# 1-Schematic_EMWAVER_V1_2.net
KiCad netlist of a schematic drawn in EasyEDA
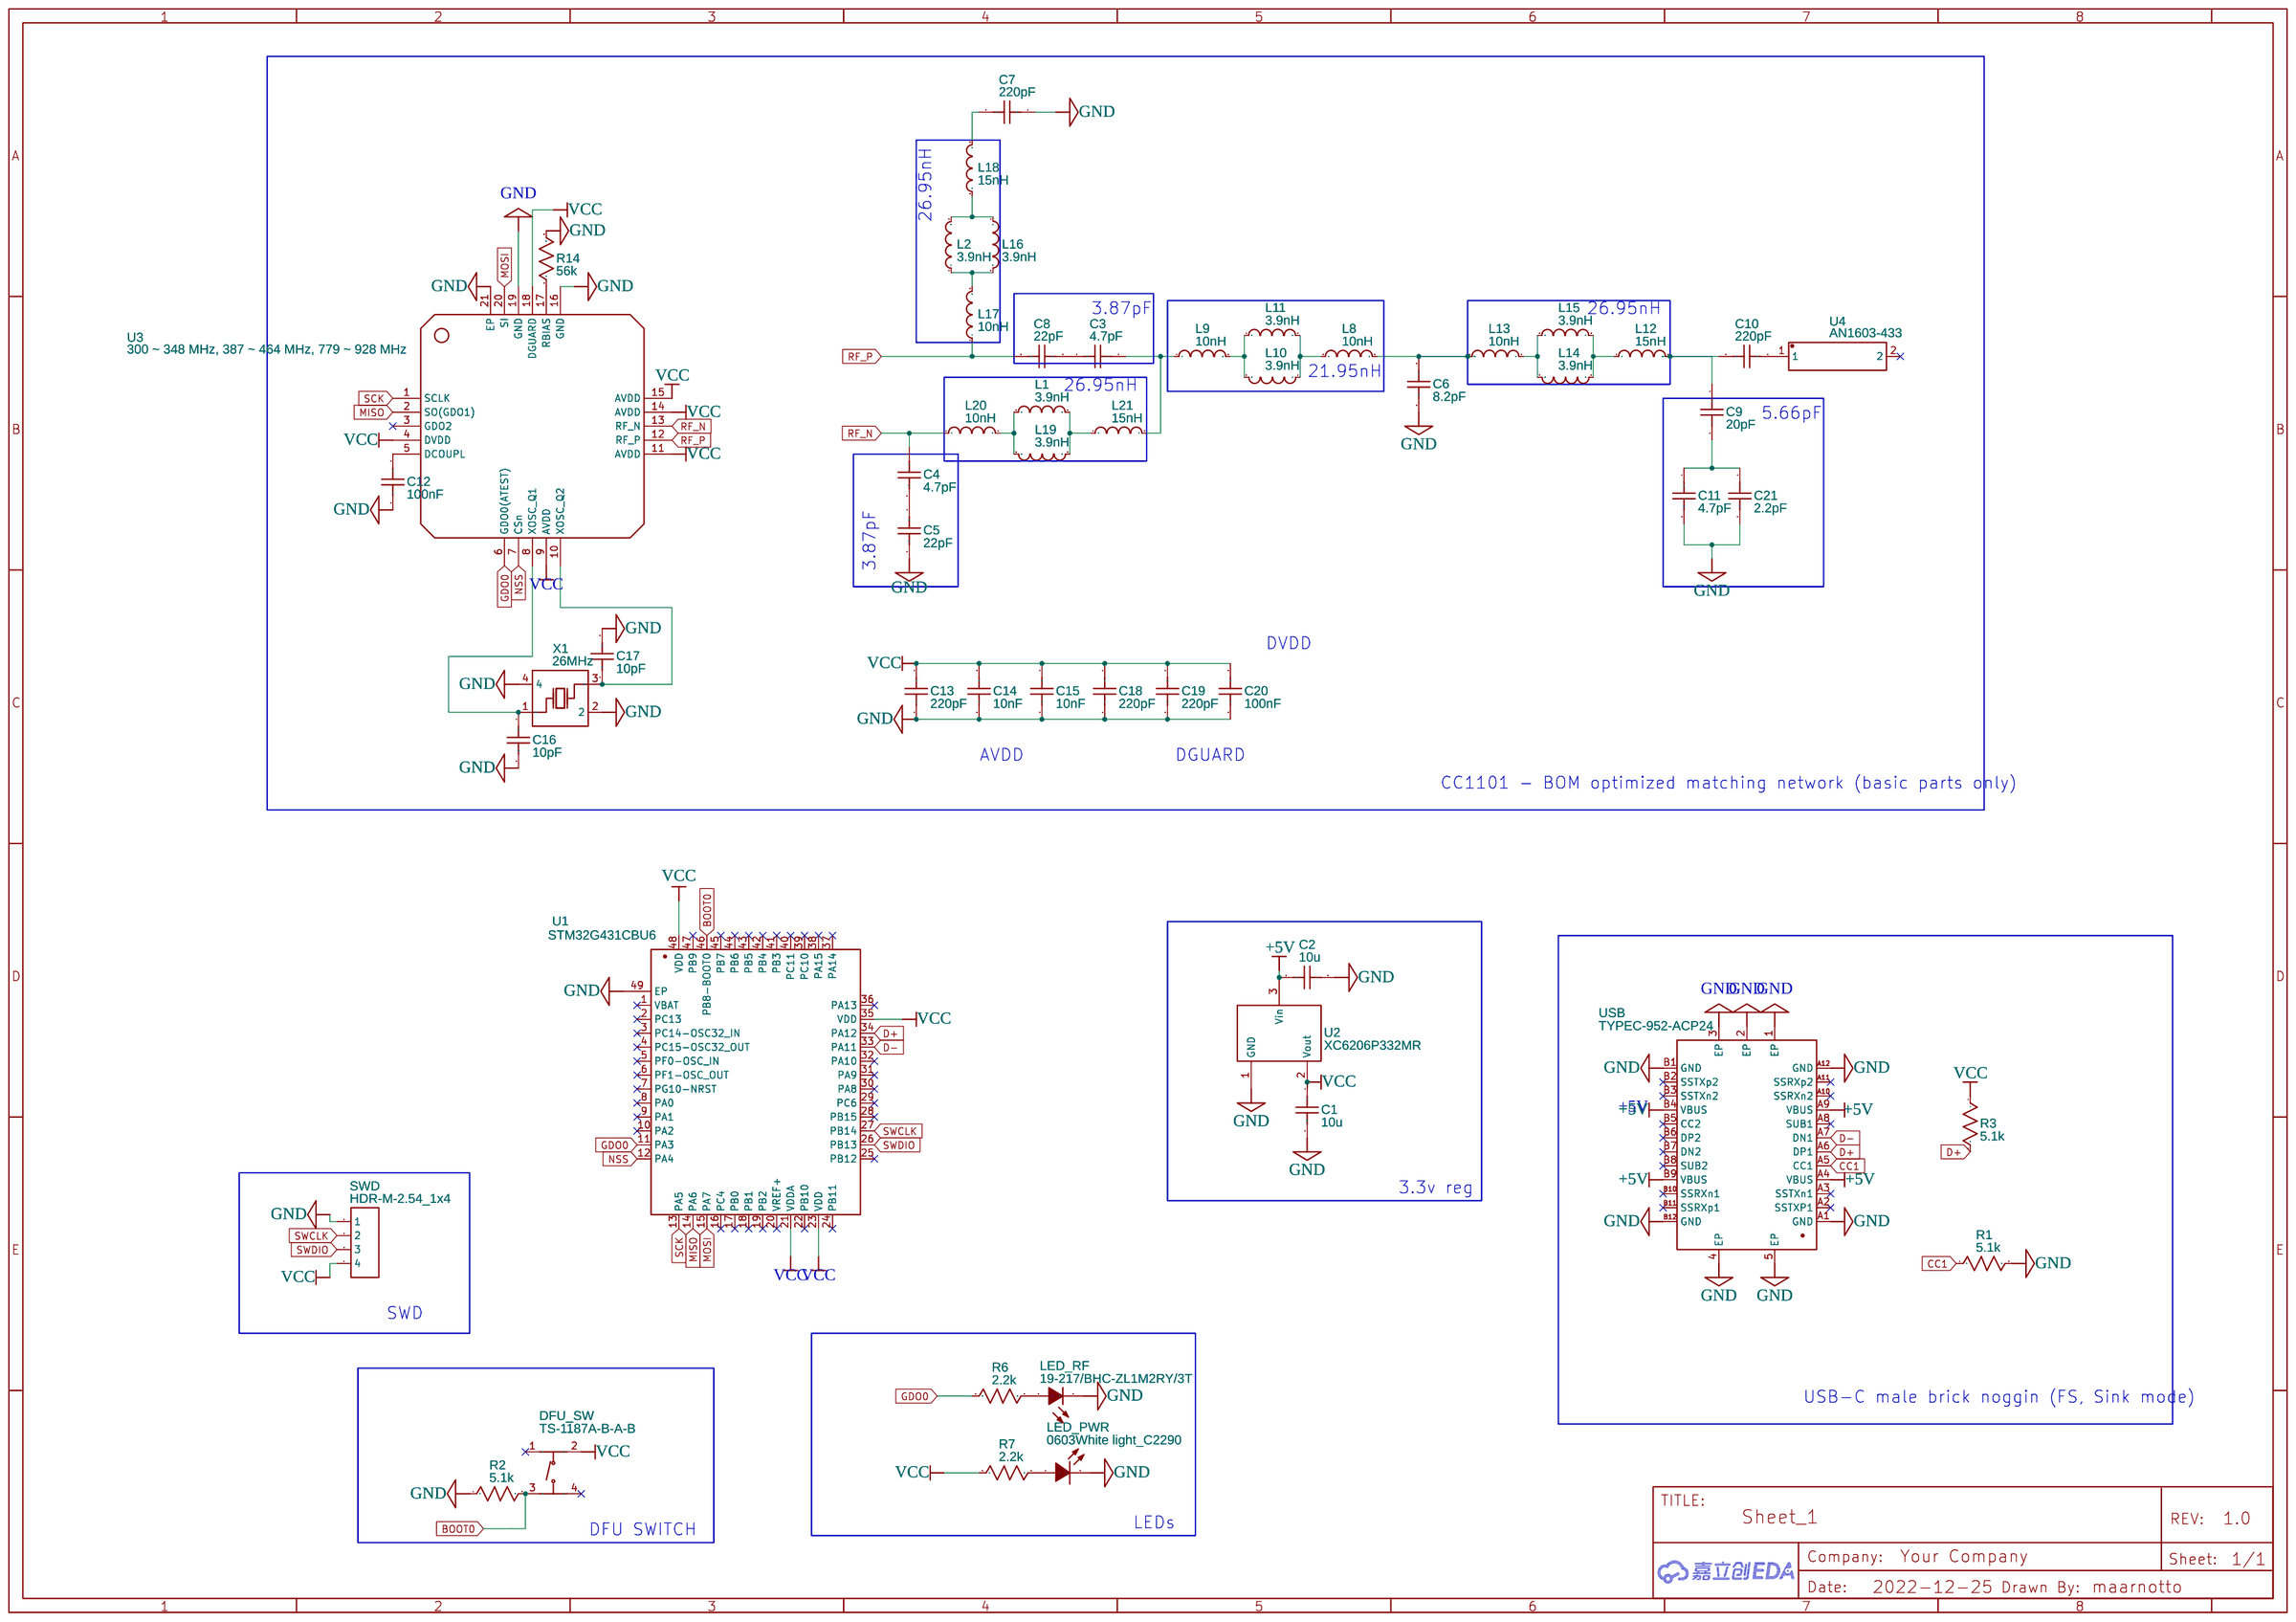
[diagram p0: schematic sheet]

(export (version "E")
  (design (tool "Eeschema 10.0.6"))
  (components
    (comp (ref "C1") (value "10u") (libsource (lib "") (part "C_0603_US_1")))
    (comp (ref "C2") (value "10u") (libsource (lib "") (part "C_0603_US")))
    (comp (ref "C3") (value "4.7pF") (libsource (lib "") (part "C_0402_US_2")))
    (comp (ref "C4") (value "4.7pF") (libsource (lib "") (part "C_0402_US")))
    (comp (ref "C5") (value "22pF") (libsource (lib "") (part "C_0402_US")))
    (comp (ref "C6") (value "8.2pF") (libsource (lib "") (part "C_0603_US_1")))
    (comp (ref "C7") (value "220pF") (libsource (lib "") (part "C_0402_US_2")))
    (comp (ref "C8") (value "22pF") (libsource (lib "") (part "C_0402_US_2")))
    (comp (ref "C9") (value "20pF") (libsource (lib "") (part "C_0402_US")))
    (comp (ref "C10") (value "220pF") (libsource (lib "") (part "C_0402_US_2")))
    (comp (ref "C11") (value "4.7pF") (libsource (lib "") (part "C_0402_US")))
    (comp (ref "C12") (value "100nF") (libsource (lib "") (part "C_0402_US")))
    (comp (ref "C13") (value "220pF") (libsource (lib "") (part "C_0402_US")))
    (comp (ref "C14") (value "10nF") (libsource (lib "") (part "C_0402_US")))
    (comp (ref "C15") (value "10nF") (libsource (lib "") (part "C_0402_US")))
    (comp (ref "C16") (value "10pF") (libsource (lib "") (part "C_0402_US")))
    (comp (ref "C17") (value "10pF") (libsource (lib "") (part "C_0402_US_1")))
    (comp (ref "C18") (value "220pF") (libsource (lib "") (part "C_0402_US")))
    (comp (ref "C19") (value "220pF") (libsource (lib "") (part "C_0402_US")))
    (comp (ref "C20") (value "100nF") (libsource (lib "") (part "C_0402_US")))
    (comp (ref "C21") (value "2.2pF") (libsource (lib "") (part "C_0402_US")))
    (comp (ref "DFU_SW")
      (value "TS-1187A-B-A-B")
      (fields (field (name "BOM_Supplier Part") "C318884"))
      (libsource (lib "") (part "TS-1187A-B-A-B"))
    )
    (comp (ref "L1")
      (value "3.9nH")
      (fields (field (name "BOM_Supplier Part") "C14033"))
      (libsource (lib "") (part "L0402_US_1"))
    )
    (comp (ref "L2")
      (value "3.9nH")
      (fields (field (name "BOM_Supplier Part") "C14033"))
      (libsource (lib "") (part "L0402_US"))
    )
    (comp (ref "L8")
      (value "10nH")
      (fields (field (name "BOM_Supplier Part") "C27147"))
      (libsource (lib "") (part "L0402_US_1"))
    )
    (comp (ref "L9")
      (value "10nH")
      (fields (field (name "BOM_Supplier Part") "C27147"))
      (libsource (lib "") (part "L0402_US_1"))
    )
    (comp (ref "L10")
      (value "3.9nH")
      (fields (field (name "BOM_Supplier Part") "C14033"))
      (libsource (lib "") (part "L0402_US_2"))
    )
    (comp (ref "L11")
      (value "3.9nH")
      (fields (field (name "BOM_Supplier Part") "C14033"))
      (libsource (lib "") (part "L0402_US_1"))
    )
    (comp (ref "L12")
      (value "15nH")
      (fields (field (name "BOM_Supplier Part") "C27143"))
      (libsource (lib "") (part "L0402_US_3"))
    )
    (comp (ref "L13")
      (value "10nH")
      (fields (field (name "BOM_Supplier Part") "C27147"))
      (libsource (lib "") (part "L0402_US_3"))
    )
    (comp (ref "L14")
      (value "3.9nH")
      (fields (field (name "BOM_Supplier Part") "C14033"))
      (libsource (lib "") (part "L0402_US_5"))
    )
    (comp (ref "L15")
      (value "3.9nH")
      (fields (field (name "BOM_Supplier Part") "C14033"))
      (libsource (lib "") (part "L0402_US_3"))
    )
    (comp (ref "L16")
      (value "3.9nH")
      (fields (field (name "BOM_Supplier Part") "C14033"))
      (libsource (lib "") (part "L0402_US_6"))
    )
    (comp (ref "L17")
      (value "10nH")
      (fields (field (name "BOM_Supplier Part") "C27147"))
      (libsource (lib "") (part "L0402_US"))
    )
    (comp (ref "L18")
      (value "15nH")
      (fields (field (name "BOM_Supplier Part") "C27143"))
      (libsource (lib "") (part "L0402_US_4"))
    )
    (comp (ref "L19")
      (value "3.9nH")
      (fields (field (name "BOM_Supplier Part") "C14033"))
      (libsource (lib "") (part "L0402_US_2"))
    )
    (comp (ref "L20")
      (value "10nH")
      (fields (field (name "BOM_Supplier Part") "C27147"))
      (libsource (lib "") (part "L0402_US_1"))
    )
    (comp (ref "L21")
      (value "15nH")
      (fields (field (name "BOM_Supplier Part") "C27143"))
      (libsource (lib "") (part "L0402_US_1"))
    )
    (comp (ref "LED_PWR")
      (value "0603White light_C2290")
      (fields (field (name "BOM_Manufacturer Part") "KT-0603白灯") (field (name "BOM_Supplier Part") "C2290"))
      (libsource (lib "") (part "0603White light_C2290"))
    )
    (comp (ref "LED_RF")
      (value "19-217/BHC-ZL1M2RY/3T")
      (fields (field (name "BOM_Supplier Part") "C72041"))
      (libsource (lib "") (part "19-217/BHC-ZL1M2RY/3T"))
    )
    (comp (ref "R1") (value "5.1k") (libsource (lib "") (part "R_0603_US")))
    (comp (ref "R2") (value "5.1k") (libsource (lib "") (part "R_0603_US")))
    (comp (ref "R3") (value "5.1k") (libsource (lib "") (part "R_0603_US_1")))
    (comp (ref "R6") (value "2.2k") (libsource (lib "") (part "R_0603_US")))
    (comp (ref "R7") (value "2.2k") (libsource (lib "") (part "R_0603_US")))
    (comp (ref "R14") (value "56k") (libsource (lib "") (part "R_0402_US")))
    (comp (ref "SWD")
      (value "HDR-M-2.54_1x4")
      (fields (field (name "BOM_Supplier Part") "C124378"))
      (libsource (lib "") (part "HDR-M-2.54_1x4"))
    )
    (comp (ref "U1")
      (value "STM32G431CBU6")
      (fields (field (name "BOM_Supplier Part") "C529356"))
      (libsource (lib "") (part "STM32G431CBU6"))
    )
    (comp (ref "U2")
      (value "XC6206P332MR")
      (fields (field (name "BOM_Supplier Part") "C5446"))
      (libsource (lib "") (part "XC6206P332MR"))
    )
    (comp (ref "U3")
      (value "300 ~ 348 MHz, 387 ~ 464 MHz, 779 ~ 928 MHz")
      (fields (field (name "BOM_Manufacturer Part") "CC1101RGPR") (field (name "BOM_Supplier Part") "C29953"))
      (libsource (lib "") (part "CC1101RGPR"))
    )
    (comp (ref "U4")
      (value "AN1603-433")
      (fields (field (name "BOM_Supplier Part") "C122806"))
      (libsource (lib "") (part "AN1603-433"))
    )
    (comp (ref "USB")
      (value "TYPEC-952-ACP24")
      (fields (field (name "BOM_Supplier Part") "C2840398"))
      (libsource (lib "") (part "TYPEC-952-ACP24"))
    )
    (comp (ref "X1")
      (value "26MHz")
      (fields
        (field (name "BOM_Manufacturer Part") "3S26000333")
        (field (name "BOM_Supplier Part") "C431163")
      )
      (libsource (lib "") (part "3S26000333"))
    )
  )
  (nets
    (net (code "1") (name "+5V") (class "Default")
      (node (ref "C2") (pin "2") (pinfunction "2_2") (pintype "unspecified"))
      (node (ref "U2") (pin "3") (pinfunction "Vin_3") (pintype "unspecified"))
      (node (ref "USB") (pin "A4") (pinfunction "VBUS_A4") (pintype "unspecified"))
      (node (ref "USB") (pin "A9") (pinfunction "VBUS_A9") (pintype "unspecified"))
      (node (ref "USB") (pin "B4") (pinfunction "VBUS_B4") (pintype "unspecified"))
      (node (ref "USB") (pin "B9") (pinfunction "VBUS_B9") (pintype "unspecified"))
    )
    (net (code "2") (name "BOOT0") (class "Default")
      (node (ref "DFU_SW") (pin "3") (pinfunction "C_3") (pintype "unspecified"))
      (node (ref "R2") (pin "2") (pinfunction "2_2") (pintype "unspecified"))
      (node (ref "U1") (pin "46") (pinfunction "PB8-BOOT0_46") (pintype "unspecified"))
    )
    (net (code "3") (name "CC1") (class "Default")
      (node (ref "R1") (pin "1") (pinfunction "1_1") (pintype "unspecified"))
      (node (ref "USB") (pin "A5") (pinfunction "CC1_A5") (pintype "unspecified"))
    )
    (net (code "4") (name "D+") (class "Default")
      (node (ref "R3") (pin "2") (pinfunction "2_2") (pintype "unspecified"))
      (node (ref "U1") (pin "34") (pinfunction "PA12_34") (pintype "unspecified"))
      (node (ref "USB") (pin "A6") (pinfunction "DP1_A6") (pintype "unspecified"))
    )
    (net (code "5") (name "D-") (class "Default")
      (node (ref "U1") (pin "33") (pinfunction "PA11_33") (pintype "unspecified"))
      (node (ref "USB") (pin "A7") (pinfunction "DN1_A7") (pintype "unspecified"))
    )
    (net (code "6") (name "GDO0") (class "Default")
      (node (ref "R6") (pin "1") (pinfunction "1_1") (pintype "unspecified"))
      (node (ref "U1") (pin "11") (pinfunction "PA3_11") (pintype "unspecified"))
      (node (ref "U3") (pin "6") (pinfunction "GDO0(ATEST)_6") (pintype "unspecified"))
    )
    (net (code "7") (name "GND") (class "Default")
      (node (ref "C1") (pin "2") (pinfunction "2_2") (pintype "unspecified"))
      (node (ref "C11") (pin "2") (pinfunction "2_2") (pintype "unspecified"))
      (node (ref "C12") (pin "2") (pinfunction "2_2") (pintype "unspecified"))
      (node (ref "C13") (pin "2") (pinfunction "2_2") (pintype "unspecified"))
      (node (ref "C14") (pin "2") (pinfunction "2_2") (pintype "unspecified"))
      (node (ref "C15") (pin "2") (pinfunction "2_2") (pintype "unspecified"))
      (node (ref "C16") (pin "2") (pinfunction "2_2") (pintype "unspecified"))
      (node (ref "C17") (pin "2") (pinfunction "2_2") (pintype "unspecified"))
      (node (ref "C18") (pin "2") (pinfunction "2_2") (pintype "unspecified"))
      (node (ref "C19") (pin "2") (pinfunction "2_2") (pintype "unspecified"))
      (node (ref "C2") (pin "1") (pinfunction "1_1") (pintype "unspecified"))
      (node (ref "C20") (pin "2") (pinfunction "2_2") (pintype "unspecified"))
      (node (ref "C21") (pin "2") (pinfunction "2_2") (pintype "unspecified"))
      (node (ref "C5") (pin "2") (pinfunction "2_2") (pintype "unspecified"))
      (node (ref "C6") (pin "2") (pinfunction "2_2") (pintype "unspecified"))
      (node (ref "C7") (pin "1") (pinfunction "1_1") (pintype "unspecified"))
      (node (ref "LED_PWR") (pin "2") (pinfunction "K_2") (pintype "unspecified"))
      (node (ref "LED_RF") (pin "1") (pinfunction "C_1") (pintype "input"))
      (node (ref "R1") (pin "2") (pinfunction "2_2") (pintype "unspecified"))
      (node (ref "R14") (pin "2") (pinfunction "2_2") (pintype "unspecified"))
      (node (ref "R2") (pin "1") (pinfunction "1_1") (pintype "unspecified"))
      (node (ref "SWD") (pin "1") (pinfunction "1_1") (pintype "unspecified"))
      (node (ref "U1") (pin "49") (pinfunction "EP_49") (pintype "unspecified"))
      (node (ref "U2") (pin "1") (pinfunction "GND_1") (pintype "unspecified"))
      (node (ref "U3") (pin "16") (pinfunction "GND_16") (pintype "unspecified"))
      (node (ref "U3") (pin "19") (pinfunction "GND_19") (pintype "unspecified"))
      (node (ref "U3") (pin "21") (pinfunction "EP_21") (pintype "unspecified"))
      (node (ref "USB") (pin "1") (pinfunction "EP_1") (pintype "unspecified"))
      (node (ref "USB") (pin "2") (pinfunction "EP_2") (pintype "unspecified"))
      (node (ref "USB") (pin "3") (pinfunction "EP_3") (pintype "unspecified"))
      (node (ref "USB") (pin "4") (pinfunction "EP_4") (pintype "unspecified"))
      (node (ref "USB") (pin "5") (pinfunction "EP_5") (pintype "unspecified"))
      (node (ref "USB") (pin "A1") (pinfunction "GND_A1") (pintype "unspecified"))
      (node (ref "USB") (pin "A12") (pinfunction "GND_A12") (pintype "unspecified"))
      (node (ref "USB") (pin "B1") (pinfunction "GND_B1") (pintype "unspecified"))
      (node (ref "USB") (pin "B12") (pinfunction "GND_B12") (pintype "unspecified"))
      (node (ref "X1") (pin "2") (pinfunction "2_2") (pintype "unspecified"))
      (node (ref "X1") (pin "4") (pinfunction "4_4") (pintype "unspecified"))
    )
    (net (code "8") (name "MISO") (class "Default")
      (node (ref "U1") (pin "14") (pinfunction "PA6_14") (pintype "unspecified"))
      (node (ref "U3") (pin "2") (pinfunction "SO(GDO1)_2") (pintype "unspecified"))
    )
    (net (code "9") (name "MOSI") (class "Default")
      (node (ref "U1") (pin "15") (pinfunction "PA7_15") (pintype "unspecified"))
      (node (ref "U3") (pin "20") (pinfunction "SI_20") (pintype "unspecified"))
    )
    (net (code "10") (name "NSS") (class "Default")
      (node (ref "U1") (pin "12") (pinfunction "PA4_12") (pintype "unspecified"))
      (node (ref "U3") (pin "7") (pinfunction "CSn_7") (pintype "unspecified"))
    )
    (net (code "11") (name "Net-(C3-Pad1)") (class "Default")
      (node (ref "C3") (pin "1") (pinfunction "1_1") (pintype "unspecified"))
      (node (ref "L21") (pin "2") (pinfunction "2_2") (pintype "unspecified"))
      (node (ref "L9") (pin "1") (pinfunction "1_1") (pintype "unspecified"))
    )
    (net (code "12") (name "Net-(C3-Pad2)") (class "Default")
      (node (ref "C3") (pin "2") (pinfunction "2_2") (pintype "unspecified"))
      (node (ref "C8") (pin "1") (pinfunction "1_1") (pintype "unspecified"))
    )
    (net (code "13") (name "Net-(C4-Pad2)") (class "Default")
      (node (ref "C4") (pin "2") (pinfunction "2_2") (pintype "unspecified"))
      (node (ref "C5") (pin "1") (pinfunction "1_1") (pintype "unspecified"))
    )
    (net (code "14") (name "Net-(C6-Pad1)") (class "Default")
      (node (ref "C6") (pin "1") (pinfunction "1_1") (pintype "unspecified"))
      (node (ref "L13") (pin "1") (pinfunction "1_1") (pintype "unspecified"))
      (node (ref "L8") (pin "2") (pinfunction "2_2") (pintype "unspecified"))
    )
    (net (code "15") (name "Net-(C7-Pad2)") (class "Default")
      (node (ref "C7") (pin "2") (pinfunction "2_2") (pintype "unspecified"))
      (node (ref "L18") (pin "2") (pinfunction "2_2") (pintype "unspecified"))
    )
    (net (code "16") (name "Net-(C10-Pad1)") (class "Default")
      (node (ref "C10") (pin "1") (pinfunction "1_1") (pintype "unspecified"))
      (node (ref "U4") (pin "1") (pinfunction "1_1") (pintype "unspecified"))
    )
    (net (code "17") (name "Net-(C10-Pad2)") (class "Default")
      (node (ref "C10") (pin "2") (pinfunction "2_2") (pintype "unspecified"))
      (node (ref "C9") (pin "1") (pinfunction "1_1") (pintype "unspecified"))
      (node (ref "L12") (pin "2") (pinfunction "2_2") (pintype "unspecified"))
    )
    (net (code "18") (name "Net-(C11-Pad1)") (class "Default")
      (node (ref "C11") (pin "1") (pinfunction "1_1") (pintype "unspecified"))
      (node (ref "C21") (pin "1") (pinfunction "1_1") (pintype "unspecified"))
      (node (ref "C9") (pin "2") (pinfunction "2_2") (pintype "unspecified"))
    )
    (net (code "19") (name "Net-(L1-Pad1)") (class "Default")
      (node (ref "L1") (pin "1") (pinfunction "1_1") (pintype "unspecified"))
      (node (ref "L19") (pin "2") (pinfunction "2_2") (pintype "unspecified"))
      (node (ref "L20") (pin "2") (pinfunction "2_2") (pintype "unspecified"))
    )
    (net (code "20") (name "Net-(L1-Pad2)") (class "Default")
      (node (ref "L1") (pin "2") (pinfunction "2_2") (pintype "unspecified"))
      (node (ref "L19") (pin "1") (pinfunction "1_1") (pintype "unspecified"))
      (node (ref "L21") (pin "1") (pinfunction "1_1") (pintype "unspecified"))
    )
    (net (code "21") (name "Net-(L10-Pad1)") (class "Default")
      (node (ref "L10") (pin "1") (pinfunction "1_1") (pintype "unspecified"))
      (node (ref "L11") (pin "2") (pinfunction "2_2") (pintype "unspecified"))
      (node (ref "L8") (pin "1") (pinfunction "1_1") (pintype "unspecified"))
    )
    (net (code "22") (name "Net-(L10-Pad2)") (class "Default")
      (node (ref "L10") (pin "2") (pinfunction "2_2") (pintype "unspecified"))
      (node (ref "L11") (pin "1") (pinfunction "1_1") (pintype "unspecified"))
      (node (ref "L9") (pin "2") (pinfunction "2_2") (pintype "unspecified"))
    )
    (net (code "23") (name "Net-(L12-Pad1)") (class "Default")
      (node (ref "L12") (pin "1") (pinfunction "1_1") (pintype "unspecified"))
      (node (ref "L14") (pin "1") (pinfunction "1_1") (pintype "unspecified"))
      (node (ref "L15") (pin "2") (pinfunction "2_2") (pintype "unspecified"))
    )
    (net (code "24") (name "Net-(L13-Pad2)") (class "Default")
      (node (ref "L13") (pin "2") (pinfunction "2_2") (pintype "unspecified"))
      (node (ref "L14") (pin "2") (pinfunction "2_2") (pintype "unspecified"))
      (node (ref "L15") (pin "1") (pinfunction "1_1") (pintype "unspecified"))
    )
    (net (code "25") (name "Net-(L16-Pad1)") (class "Default")
      (node (ref "L16") (pin "1") (pinfunction "1_1") (pintype "unspecified"))
      (node (ref "L18") (pin "1") (pinfunction "1_1") (pintype "unspecified"))
      (node (ref "L2") (pin "2") (pinfunction "2_2") (pintype "unspecified"))
    )
    (net (code "26") (name "Net-(L16-Pad2)") (class "Default")
      (node (ref "L16") (pin "2") (pinfunction "2_2") (pintype "unspecified"))
      (node (ref "L17") (pin "2") (pinfunction "2_2") (pintype "unspecified"))
      (node (ref "L2") (pin "1") (pinfunction "1_1") (pintype "unspecified"))
    )
    (net (code "27") (name "Net-(LED_PWR-A)") (class "Default")
      (node (ref "LED_PWR") (pin "1") (pinfunction "A_1") (pintype "unspecified"))
      (node (ref "R7") (pin "2") (pinfunction "2_2") (pintype "unspecified"))
    )
    (net (code "28") (name "Net-(LED_RF-A)") (class "Default")
      (node (ref "LED_RF") (pin "2") (pinfunction "A_2") (pintype "input"))
      (node (ref "R6") (pin "2") (pinfunction "2_2") (pintype "unspecified"))
    )
    (net (code "29") (name "Net-(U3-DCOUPL)") (class "Default")
      (node (ref "C12") (pin "1") (pinfunction "1_1") (pintype "unspecified"))
      (node (ref "U3") (pin "5") (pinfunction "DCOUPL_5") (pintype "unspecified"))
    )
    (net (code "30") (name "Net-(U3-RBIAS)") (class "Default")
      (node (ref "R14") (pin "1") (pinfunction "1_1") (pintype "unspecified"))
      (node (ref "U3") (pin "17") (pinfunction "RBIAS_17") (pintype "unspecified"))
    )
    (net (code "31") (name "Net-(U3-XOSC_Q1)") (class "Default")
      (node (ref "C16") (pin "1") (pinfunction "1_1") (pintype "unspecified"))
      (node (ref "U3") (pin "8") (pinfunction "XOSC_Q1_8") (pintype "unspecified"))
      (node (ref "X1") (pin "1") (pinfunction "OSC1_1") (pintype "unspecified"))
    )
    (net (code "32") (name "Net-(U3-XOSC_Q2)") (class "Default")
      (node (ref "C17") (pin "1") (pinfunction "1_1") (pintype "unspecified"))
      (node (ref "U3") (pin "10") (pinfunction "XOSC_Q2_10") (pintype "unspecified"))
      (node (ref "X1") (pin "3") (pinfunction "OSC2_3") (pintype "unspecified"))
    )
    (net (code "33") (name "RF_N") (class "Default")
      (node (ref "C4") (pin "1") (pinfunction "1_1") (pintype "unspecified"))
      (node (ref "L20") (pin "1") (pinfunction "1_1") (pintype "unspecified"))
      (node (ref "U3") (pin "13") (pinfunction "RF_N_13") (pintype "unspecified"))
    )
    (net (code "34") (name "RF_P") (class "Default")
      (node (ref "C8") (pin "2") (pinfunction "2_2") (pintype "unspecified"))
      (node (ref "L17") (pin "1") (pinfunction "1_1") (pintype "unspecified"))
      (node (ref "U3") (pin "12") (pinfunction "RF_P_12") (pintype "unspecified"))
    )
    (net (code "35") (name "SCK") (class "Default")
      (node (ref "U1") (pin "13") (pinfunction "PA5_13") (pintype "unspecified"))
      (node (ref "U3") (pin "1") (pinfunction "SCLK_1") (pintype "unspecified"))
    )
    (net (code "36") (name "SWCLK") (class "Default")
      (node (ref "SWD") (pin "2") (pinfunction "2_2") (pintype "unspecified"))
      (node (ref "U1") (pin "27") (pinfunction "PB14_27") (pintype "unspecified"))
    )
    (net (code "37") (name "SWDIO") (class "Default")
      (node (ref "SWD") (pin "3") (pinfunction "3_3") (pintype "unspecified"))
      (node (ref "U1") (pin "26") (pinfunction "PB13_26") (pintype "unspecified"))
    )
    (net (code "38") (name "VCC") (class "Default")
      (node (ref "C1") (pin "1") (pinfunction "1_1") (pintype "unspecified"))
      (node (ref "C13") (pin "1") (pinfunction "1_1") (pintype "unspecified"))
      (node (ref "C14") (pin "1") (pinfunction "1_1") (pintype "unspecified"))
      (node (ref "C15") (pin "1") (pinfunction "1_1") (pintype "unspecified"))
      (node (ref "C18") (pin "1") (pinfunction "1_1") (pintype "unspecified"))
      (node (ref "C19") (pin "1") (pinfunction "1_1") (pintype "unspecified"))
      (node (ref "C20") (pin "1") (pinfunction "1_1") (pintype "unspecified"))
      (node (ref "DFU_SW") (pin "2") (pinfunction "B_2") (pintype "unspecified"))
      (node (ref "R3") (pin "1") (pinfunction "1_1") (pintype "unspecified"))
      (node (ref "R7") (pin "1") (pinfunction "1_1") (pintype "unspecified"))
      (node (ref "SWD") (pin "4") (pinfunction "4_4") (pintype "unspecified"))
      (node (ref "U1") (pin "21") (pinfunction "VDDA_21") (pintype "unspecified"))
      (node (ref "U1") (pin "23") (pinfunction "VDD_23") (pintype "unspecified"))
      (node (ref "U1") (pin "35") (pinfunction "VDD_35") (pintype "unspecified"))
      (node (ref "U1") (pin "48") (pinfunction "VDD_48") (pintype "unspecified"))
      (node (ref "U2") (pin "2") (pinfunction "Vout_2") (pintype "unspecified"))
      (node (ref "U3") (pin "11") (pinfunction "AVDD_11") (pintype "unspecified"))
      (node (ref "U3") (pin "14") (pinfunction "AVDD_14") (pintype "unspecified"))
      (node (ref "U3") (pin "15") (pinfunction "AVDD_15") (pintype "unspecified"))
      (node (ref "U3") (pin "18") (pinfunction "DGUARD_18") (pintype "unspecified"))
      (node (ref "U3") (pin "4") (pinfunction "DVDD_4") (pintype "unspecified"))
      (node (ref "U3") (pin "9") (pinfunction "AVDD_9") (pintype "unspecified"))
    )
    (net (code "39") (name "unconnected-(DFU_SW-A-Pad1)") (class "Default")
      (node (ref "DFU_SW") (pin "1") (pinfunction "A_1") (pintype "unspecified+no_connect"))
    )
    (net (code "40") (name "unconnected-(DFU_SW-D-Pad4)") (class "Default")
      (node (ref "DFU_SW") (pin "4") (pinfunction "D_4") (pintype "unspecified+no_connect"))
    )
    (net (code "41") (name "unconnected-(U1-PA0-Pad8)") (class "Default")
      (node (ref "U1") (pin "8") (pinfunction "PA0_8") (pintype "unspecified+no_connect"))
    )
    (net (code "42") (name "unconnected-(U1-PA1-Pad9)") (class "Default")
      (node (ref "U1") (pin "9") (pinfunction "PA1_9") (pintype "unspecified+no_connect"))
    )
    (net (code "43") (name "unconnected-(U1-PA2-Pad10)") (class "Default")
      (node (ref "U1") (pin "10") (pinfunction "PA2_10") (pintype "unspecified+no_connect"))
    )
    (net (code "44") (name "unconnected-(U1-PA8-Pad30)") (class "Default")
      (node (ref "U1") (pin "30") (pinfunction "PA8_30") (pintype "unspecified+no_connect"))
    )
    (net (code "45") (name "unconnected-(U1-PA9-Pad31)") (class "Default")
      (node (ref "U1") (pin "31") (pinfunction "PA9_31") (pintype "unspecified+no_connect"))
    )
    (net (code "46") (name "unconnected-(U1-PA10-Pad32)") (class "Default")
      (node (ref "U1") (pin "32") (pinfunction "PA10_32") (pintype "unspecified+no_connect"))
    )
    (net (code "47") (name "unconnected-(U1-PA13-Pad36)") (class "Default")
      (node (ref "U1") (pin "36") (pinfunction "PA13_36") (pintype "unspecified+no_connect"))
    )
    (net (code "48") (name "unconnected-(U1-PA14-Pad37)") (class "Default")
      (node (ref "U1") (pin "37") (pinfunction "PA14_37") (pintype "unspecified+no_connect"))
    )
    (net (code "49") (name "unconnected-(U1-PA15-Pad38)") (class "Default")
      (node (ref "U1") (pin "38") (pinfunction "PA15_38") (pintype "unspecified+no_connect"))
    )
    (net (code "50") (name "unconnected-(U1-PB0-Pad17)") (class "Default")
      (node (ref "U1") (pin "17") (pinfunction "PB0_17") (pintype "unspecified+no_connect"))
    )
    (net (code "51") (name "unconnected-(U1-PB1-Pad18)") (class "Default")
      (node (ref "U1") (pin "18") (pinfunction "PB1_18") (pintype "unspecified+no_connect"))
    )
    (net (code "52") (name "unconnected-(U1-PB2-Pad19)") (class "Default")
      (node (ref "U1") (pin "19") (pinfunction "PB2_19") (pintype "unspecified+no_connect"))
    )
    (net (code "53") (name "unconnected-(U1-PB3-Pad41)") (class "Default")
      (node (ref "U1") (pin "41") (pinfunction "PB3_41") (pintype "unspecified+no_connect"))
    )
    (net (code "54") (name "unconnected-(U1-PB4-Pad42)") (class "Default")
      (node (ref "U1") (pin "42") (pinfunction "PB4_42") (pintype "unspecified+no_connect"))
    )
    (net (code "55") (name "unconnected-(U1-PB5-Pad43)") (class "Default")
      (node (ref "U1") (pin "43") (pinfunction "PB5_43") (pintype "unspecified+no_connect"))
    )
    (net (code "56") (name "unconnected-(U1-PB6-Pad44)") (class "Default")
      (node (ref "U1") (pin "44") (pinfunction "PB6_44") (pintype "unspecified+no_connect"))
    )
    (net (code "57") (name "unconnected-(U1-PB7-Pad45)") (class "Default")
      (node (ref "U1") (pin "45") (pinfunction "PB7_45") (pintype "unspecified+no_connect"))
    )
    (net (code "58") (name "unconnected-(U1-PB9-Pad47)") (class "Default")
      (node (ref "U1") (pin "47") (pinfunction "PB9_47") (pintype "unspecified+no_connect"))
    )
    (net (code "59") (name "unconnected-(U1-PB10-Pad22)") (class "Default")
      (node (ref "U1") (pin "22") (pinfunction "PB10_22") (pintype "unspecified+no_connect"))
    )
    (net (code "60") (name "unconnected-(U1-PB11-Pad24)") (class "Default")
      (node (ref "U1") (pin "24") (pinfunction "PB11_24") (pintype "unspecified+no_connect"))
    )
    (net (code "61") (name "unconnected-(U1-PB12-Pad25)") (class "Default")
      (node (ref "U1") (pin "25") (pinfunction "PB12_25") (pintype "unspecified+no_connect"))
    )
    (net (code "62") (name "unconnected-(U1-PB15-Pad28)") (class "Default")
      (node (ref "U1") (pin "28") (pinfunction "PB15_28") (pintype "unspecified+no_connect"))
    )
    (net (code "63") (name "unconnected-(U1-PC4-Pad16)") (class "Default")
      (node (ref "U1") (pin "16") (pinfunction "PC4_16") (pintype "unspecified+no_connect"))
    )
    (net (code "64") (name "unconnected-(U1-PC6-Pad29)") (class "Default")
      (node (ref "U1") (pin "29") (pinfunction "PC6_29") (pintype "unspecified+no_connect"))
    )
    (net (code "65") (name "unconnected-(U1-PC10-Pad39)") (class "Default")
      (node (ref "U1") (pin "39") (pinfunction "PC10_39") (pintype "unspecified+no_connect"))
    )
    (net (code "66") (name "unconnected-(U1-PC11-Pad40)") (class "Default")
      (node (ref "U1") (pin "40") (pinfunction "PC11_40") (pintype "unspecified+no_connect"))
    )
    (net (code "67") (name "unconnected-(U1-PC13-Pad2)") (class "Default")
      (node (ref "U1") (pin "2") (pinfunction "PC13_2") (pintype "unspecified+no_connect"))
    )
    (net (code "68") (name "unconnected-(U1-PC14-OSC32_IN-Pad3)") (class "Default")
      (node (ref "U1") (pin "3") (pinfunction "PC14-OSC32_IN_3") (pintype "unspecified+no_connect"))
    )
    (net (code "69") (name "unconnected-(U1-PC15-OSC32_OUT-Pad4)") (class "Default")
      (node (ref "U1") (pin "4") (pinfunction "PC15-OSC32_OUT_4") (pintype "unspecified+no_connect"))
    )
    (net (code "70") (name "unconnected-(U1-PF0-OSC_IN-Pad5)") (class "Default")
      (node (ref "U1") (pin "5") (pinfunction "PF0-OSC_IN_5") (pintype "unspecified+no_connect"))
    )
    (net (code "71") (name "unconnected-(U1-PF1-OSC_OUT-Pad6)") (class "Default")
      (node (ref "U1") (pin "6") (pinfunction "PF1-OSC_OUT_6") (pintype "unspecified+no_connect"))
    )
    (net (code "72") (name "unconnected-(U1-PG10-NRST-Pad7)") (class "Default")
      (node (ref "U1") (pin "7") (pinfunction "PG10-NRST_7") (pintype "unspecified+no_connect"))
    )
    (net (code "73") (name "unconnected-(U1-VBAT-Pad1)") (class "Default")
      (node (ref "U1") (pin "1") (pinfunction "VBAT_1") (pintype "unspecified+no_connect"))
    )
    (net (code "74") (name "unconnected-(U1-VREF+-Pad20)") (class "Default")
      (node (ref "U1") (pin "20") (pinfunction "VREF+_20") (pintype "unspecified+no_connect"))
    )
    (net (code "75") (name "unconnected-(U3-GDO2-Pad3)") (class "Default")
      (node (ref "U3") (pin "3") (pinfunction "GDO2_3") (pintype "unspecified+no_connect"))
    )
    (net (code "76") (name "unconnected-(U4-Pad2)") (class "Default")
      (node (ref "U4") (pin "2") (pinfunction "2_2") (pintype "unspecified+no_connect"))
    )
    (net (code "77") (name "unconnected-(USB-CC2-PadB5)") (class "Default")
      (node (ref "USB") (pin "B5") (pinfunction "CC2_B5") (pintype "unspecified+no_connect"))
    )
    (net (code "78") (name "unconnected-(USB-DN2-PadB7)") (class "Default")
      (node (ref "USB") (pin "B7") (pinfunction "DN2_B7") (pintype "unspecified+no_connect"))
    )
    (net (code "79") (name "unconnected-(USB-DP2-PadB6)") (class "Default")
      (node (ref "USB") (pin "B6") (pinfunction "DP2_B6") (pintype "unspecified+no_connect"))
    )
    (net (code "80") (name "unconnected-(USB-SSRXn1-PadB10)") (class "Default")
      (node (ref "USB") (pin "B10") (pinfunction "SSRXn1_B10") (pintype "unspecified+no_connect"))
    )
    (net (code "81") (name "unconnected-(USB-SSRXn2-PadA10)") (class "Default")
      (node (ref "USB") (pin "A10") (pinfunction "SSRXn2_A10") (pintype "unspecified+no_connect"))
    )
    (net (code "82") (name "unconnected-(USB-SSRXp1-PadB11)") (class "Default")
      (node (ref "USB") (pin "B11") (pinfunction "SSRXp1_B11") (pintype "unspecified+no_connect"))
    )
    (net (code "83") (name "unconnected-(USB-SSRXp2-PadA11)") (class "Default")
      (node (ref "USB") (pin "A11") (pinfunction "SSRXp2_A11") (pintype "unspecified+no_connect"))
    )
    (net (code "84") (name "unconnected-(USB-SSTXP1-PadA2)") (class "Default")
      (node (ref "USB") (pin "A2") (pinfunction "SSTXP1_A2") (pintype "unspecified+no_connect"))
    )
    (net (code "85") (name "unconnected-(USB-SSTXn1-PadA3)") (class "Default")
      (node (ref "USB") (pin "A3") (pinfunction "SSTXn1_A3") (pintype "unspecified+no_connect"))
    )
    (net (code "86") (name "unconnected-(USB-SSTXn2-PadB3)") (class "Default")
      (node (ref "USB") (pin "B3") (pinfunction "SSTXn2_B3") (pintype "unspecified+no_connect"))
    )
    (net (code "87") (name "unconnected-(USB-SSTXp2-PadB2)") (class "Default")
      (node (ref "USB") (pin "B2") (pinfunction "SSTXp2_B2") (pintype "unspecified+no_connect"))
    )
    (net (code "88") (name "unconnected-(USB-SUB1-PadA8)") (class "Default")
      (node (ref "USB") (pin "A8") (pinfunction "SUB1_A8") (pintype "unspecified+no_connect"))
    )
    (net (code "89") (name "unconnected-(USB-SUB2-PadB8)") (class "Default")
      (node (ref "USB") (pin "B8") (pinfunction "SUB2_B8") (pintype "unspecified+no_connect"))
    )
  )
)
